# BackPage.net
KiCad netlist of a schematic drawn in Altium Designer
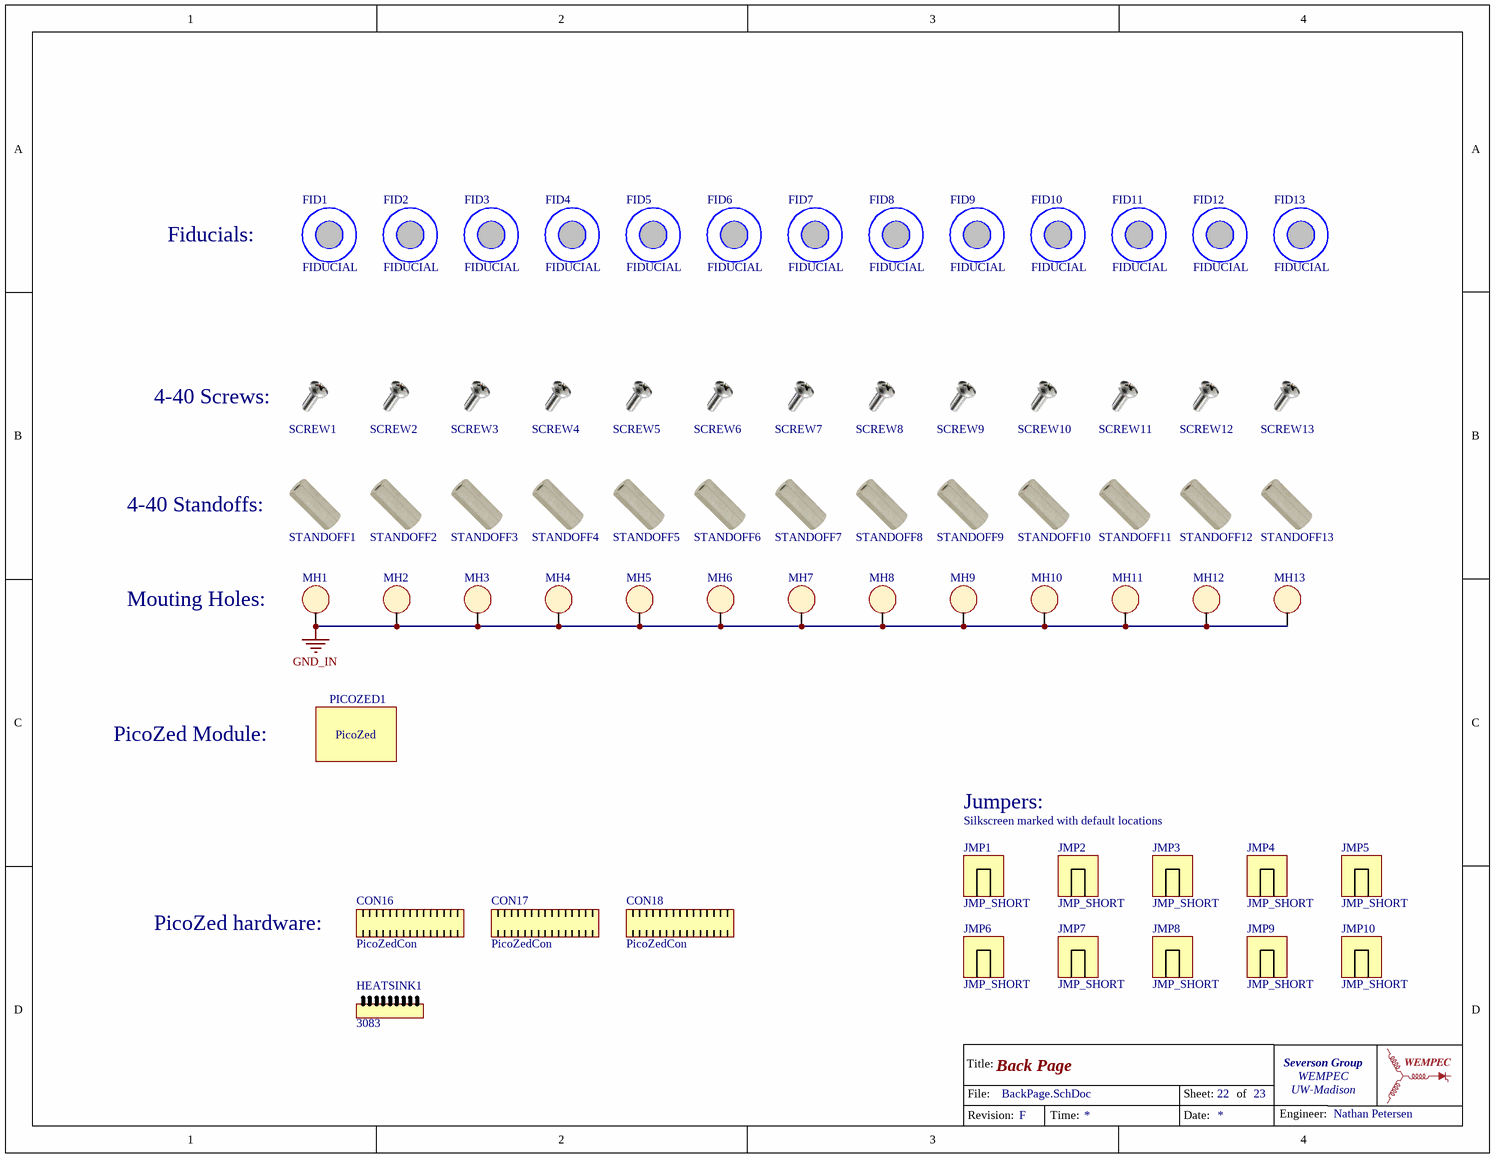
[diagram p0: BackPage.SchDoc]

(export (version "E")
  (design (tool "Eeschema 10.0.6"))
  (components
    (comp (ref "CON16")
      (value "PicoZedCon")
      (description "CONN HEADER 100POS .8MM DUAL SMD")
      (libsource (lib "AMDC") (part "PicoZedCon"))
    )
    (comp (ref "CON17")
      (value "PicoZedCon")
      (description "CONN HEADER 100POS .8MM DUAL SMD")
      (libsource (lib "AMDC") (part "PicoZedCon"))
    )
    (comp (ref "CON18")
      (value "PicoZedCon")
      (description "CONN HEADER 100POS .8MM DUAL SMD")
      (libsource (lib "AMDC") (part "PicoZedCon"))
    )
    (comp (ref "FID1") (value "FIDUCIAL") (footprint "FID_1mm") (libsource (lib "AMDC") (part "FIDUCIAL")))
    (comp (ref "FID2") (value "FIDUCIAL") (footprint "FID_1mm") (libsource (lib "AMDC") (part "FIDUCIAL")))
    (comp (ref "FID3") (value "FIDUCIAL") (footprint "FID_1mm") (libsource (lib "AMDC") (part "FIDUCIAL")))
    (comp (ref "FID4") (value "FIDUCIAL") (footprint "FID_1mm") (libsource (lib "AMDC") (part "FIDUCIAL")))
    (comp (ref "FID5") (value "FIDUCIAL") (footprint "FID_1mm") (libsource (lib "AMDC") (part "FIDUCIAL")))
    (comp (ref "FID6") (value "FIDUCIAL") (footprint "FID_1mm") (libsource (lib "AMDC") (part "FIDUCIAL")))
    (comp (ref "FID7") (value "FIDUCIAL") (footprint "FID_1mm") (libsource (lib "AMDC") (part "FIDUCIAL")))
    (comp (ref "FID8") (value "FIDUCIAL") (footprint "FID_1mm") (libsource (lib "AMDC") (part "FIDUCIAL")))
    (comp (ref "FID9") (value "FIDUCIAL") (footprint "FID_1mm") (libsource (lib "AMDC") (part "FIDUCIAL")))
    (comp (ref "FID10") (value "FIDUCIAL") (footprint "FID_1mm") (libsource (lib "AMDC") (part "FIDUCIAL")))
    (comp (ref "FID11") (value "FIDUCIAL") (footprint "FID_1mm") (libsource (lib "AMDC") (part "FIDUCIAL")))
    (comp (ref "FID12") (value "FIDUCIAL") (footprint "FID_1mm") (libsource (lib "AMDC") (part "FIDUCIAL")))
    (comp (ref "FID13") (value "FIDUCIAL") (footprint "FID_1mm") (libsource (lib "AMDC") (part "FIDUCIAL")))
    (comp (ref "HEATSINK1")
      (value "3083")
      (description "ALUM HEAT SINK FOR RASPBERRY PI")
      (libsource (lib "AMDC") (part "PicoZedHeatSink"))
    )
    (comp (ref "JMP1")
      (value "JMP_SHORT")
      (description "CONN JUMPER SHORTING .100\" GOLD")
      (libsource (lib "AMDC") (part "JUMPER_SHORT"))
    )
    (comp (ref "JMP2")
      (value "JMP_SHORT")
      (description "CONN JUMPER SHORTING .100\" GOLD")
      (libsource (lib "AMDC") (part "JUMPER_SHORT"))
    )
    (comp (ref "JMP3")
      (value "JMP_SHORT")
      (description "CONN JUMPER SHORTING .100\" GOLD")
      (libsource (lib "AMDC") (part "JUMPER_SHORT"))
    )
    (comp (ref "JMP4")
      (value "JMP_SHORT")
      (description "CONN JUMPER SHORTING .100\" GOLD")
      (libsource (lib "AMDC") (part "JUMPER_SHORT"))
    )
    (comp (ref "JMP5")
      (value "JMP_SHORT")
      (description "CONN JUMPER SHORTING .100\" GOLD")
      (libsource (lib "AMDC") (part "JUMPER_SHORT"))
    )
    (comp (ref "JMP6")
      (value "JMP_SHORT")
      (description "CONN JUMPER SHORTING .100\" GOLD")
      (libsource (lib "AMDC") (part "JUMPER_SHORT"))
    )
    (comp (ref "JMP7")
      (value "JMP_SHORT")
      (description "CONN JUMPER SHORTING .100\" GOLD")
      (libsource (lib "AMDC") (part "JUMPER_SHORT"))
    )
    (comp (ref "JMP8")
      (value "JMP_SHORT")
      (description "CONN JUMPER SHORTING .100\" GOLD")
      (libsource (lib "AMDC") (part "JUMPER_SHORT"))
    )
    (comp (ref "JMP9")
      (value "JMP_SHORT")
      (description "CONN JUMPER SHORTING .100\" GOLD")
      (libsource (lib "AMDC") (part "JUMPER_SHORT"))
    )
    (comp (ref "JMP10")
      (value "JMP_SHORT")
      (description "CONN JUMPER SHORTING .100\" GOLD")
      (libsource (lib "AMDC") (part "JUMPER_SHORT"))
    )
    (comp (ref "MH1")
      (value "MOUNT_HOLE")
      (footprint "MOUNTING_HOLE")
      (description "MOUNTING HOLE")
      (libsource (lib "AMDC") (part "MOUNT_HOLE"))
    )
    (comp (ref "MH2")
      (value "MOUNT_HOLE")
      (footprint "MOUNTING_HOLE")
      (description "MOUNTING HOLE")
      (libsource (lib "AMDC") (part "MOUNT_HOLE"))
    )
    (comp (ref "MH3")
      (value "MOUNT_HOLE")
      (footprint "MOUNTING_HOLE")
      (description "MOUNTING HOLE")
      (libsource (lib "AMDC") (part "MOUNT_HOLE"))
    )
    (comp (ref "MH4")
      (value "MOUNT_HOLE")
      (footprint "MOUNTING_HOLE")
      (description "MOUNTING HOLE")
      (libsource (lib "AMDC") (part "MOUNT_HOLE"))
    )
    (comp (ref "MH5")
      (value "MOUNT_HOLE")
      (footprint "MOUNTING_HOLE")
      (description "MOUNTING HOLE")
      (libsource (lib "AMDC") (part "MOUNT_HOLE"))
    )
    (comp (ref "MH6")
      (value "MOUNT_HOLE")
      (footprint "MOUNTING_HOLE")
      (description "MOUNTING HOLE")
      (libsource (lib "AMDC") (part "MOUNT_HOLE"))
    )
    (comp (ref "MH7")
      (value "MOUNT_HOLE")
      (footprint "MOUNTING_HOLE")
      (description "MOUNTING HOLE")
      (libsource (lib "AMDC") (part "MOUNT_HOLE"))
    )
    (comp (ref "MH8")
      (value "MOUNT_HOLE")
      (footprint "MOUNTING_HOLE")
      (description "MOUNTING HOLE")
      (libsource (lib "AMDC") (part "MOUNT_HOLE"))
    )
    (comp (ref "MH9")
      (value "MOUNT_HOLE")
      (footprint "MOUNTING_HOLE")
      (description "MOUNTING HOLE")
      (libsource (lib "AMDC") (part "MOUNT_HOLE"))
    )
    (comp (ref "MH10")
      (value "MOUNT_HOLE")
      (footprint "MOUNTING_HOLE")
      (description "MOUNTING HOLE")
      (libsource (lib "AMDC") (part "MOUNT_HOLE"))
    )
    (comp (ref "MH11")
      (value "MOUNT_HOLE")
      (footprint "MOUNTING_HOLE")
      (description "MOUNTING HOLE")
      (libsource (lib "AMDC") (part "MOUNT_HOLE"))
    )
    (comp (ref "MH12")
      (value "MOUNT_HOLE")
      (footprint "MOUNTING_HOLE")
      (description "MOUNTING HOLE")
      (libsource (lib "AMDC") (part "MOUNT_HOLE"))
    )
    (comp (ref "MH13")
      (value "MOUNT_HOLE")
      (footprint "MOUNTING_HOLE")
      (description "MOUNTING HOLE")
      (libsource (lib "AMDC") (part "MOUNT_HOLE"))
    )
    (comp (ref "PICOZED1")
      (value "7Z030-PicoZed")
      (description "PicoZed 7030 SOM Evaluation Board with ARM Cortex-A9 1 x 10/100/1000 eMMC/QSPI Flash")
      (libsource (lib "AMDC") (part "7Z030-PicoZed"))
    )
    (comp (ref "SCREW1") (value "Screw-4-40") (libsource (lib "AMDC") (part "Screw-4-40")))
    (comp (ref "SCREW2") (value "Screw-4-40") (libsource (lib "AMDC") (part "Screw-4-40")))
    (comp (ref "SCREW3") (value "Screw-4-40") (libsource (lib "AMDC") (part "Screw-4-40")))
    (comp (ref "SCREW4") (value "Screw-4-40") (libsource (lib "AMDC") (part "Screw-4-40")))
    (comp (ref "SCREW5") (value "Screw-4-40") (libsource (lib "AMDC") (part "Screw-4-40")))
    (comp (ref "SCREW6") (value "Screw-4-40") (libsource (lib "AMDC") (part "Screw-4-40")))
    (comp (ref "SCREW7") (value "Screw-4-40") (libsource (lib "AMDC") (part "Screw-4-40")))
    (comp (ref "SCREW8") (value "Screw-4-40") (libsource (lib "AMDC") (part "Screw-4-40")))
    (comp (ref "SCREW9") (value "Screw-4-40") (libsource (lib "AMDC") (part "Screw-4-40")))
    (comp (ref "SCREW10") (value "Screw-4-40") (libsource (lib "AMDC") (part "Screw-4-40")))
    (comp (ref "SCREW11") (value "Screw-4-40") (libsource (lib "AMDC") (part "Screw-4-40")))
    (comp (ref "SCREW12") (value "Screw-4-40") (libsource (lib "AMDC") (part "Screw-4-40")))
    (comp (ref "SCREW13") (value "Screw-4-40") (libsource (lib "AMDC") (part "Screw-4-40")))
    (comp (ref "STANDOFF1") (value "Standoff-4-40") (libsource (lib "AMDC") (part "Standoff-4-40")))
    (comp (ref "STANDOFF2") (value "Standoff-4-40") (libsource (lib "AMDC") (part "Standoff-4-40")))
    (comp (ref "STANDOFF3") (value "Standoff-4-40") (libsource (lib "AMDC") (part "Standoff-4-40")))
    (comp (ref "STANDOFF4") (value "Standoff-4-40") (libsource (lib "AMDC") (part "Standoff-4-40")))
    (comp (ref "STANDOFF5") (value "Standoff-4-40") (libsource (lib "AMDC") (part "Standoff-4-40")))
    (comp (ref "STANDOFF6") (value "Standoff-4-40") (libsource (lib "AMDC") (part "Standoff-4-40")))
    (comp (ref "STANDOFF7") (value "Standoff-4-40") (libsource (lib "AMDC") (part "Standoff-4-40")))
    (comp (ref "STANDOFF8") (value "Standoff-4-40") (libsource (lib "AMDC") (part "Standoff-4-40")))
    (comp (ref "STANDOFF9") (value "Standoff-4-40") (libsource (lib "AMDC") (part "Standoff-4-40")))
    (comp (ref "STANDOFF10") (value "Standoff-4-40") (libsource (lib "AMDC") (part "Standoff-4-40")))
    (comp (ref "STANDOFF11") (value "Standoff-4-40") (libsource (lib "AMDC") (part "Standoff-4-40")))
    (comp (ref "STANDOFF12") (value "Standoff-4-40") (libsource (lib "AMDC") (part "Standoff-4-40")))
    (comp (ref "STANDOFF13") (value "Standoff-4-40") (libsource (lib "AMDC") (part "Standoff-4-40")))
  )
  (nets
    (net (code "1") (name "GND_IN") (class "Default")
      (node (ref "MH1") (pin "1") (pinfunction "1_1") (pintype "passive"))
      (node (ref "MH10") (pin "1") (pinfunction "1_1") (pintype "passive"))
      (node (ref "MH11") (pin "1") (pinfunction "1_1") (pintype "passive"))
      (node (ref "MH12") (pin "1") (pinfunction "1_1") (pintype "passive"))
      (node (ref "MH13") (pin "1") (pinfunction "1_1") (pintype "passive"))
      (node (ref "MH2") (pin "1") (pinfunction "1_1") (pintype "passive"))
      (node (ref "MH3") (pin "1") (pinfunction "1_1") (pintype "passive"))
      (node (ref "MH4") (pin "1") (pinfunction "1_1") (pintype "passive"))
      (node (ref "MH5") (pin "1") (pinfunction "1_1") (pintype "passive"))
      (node (ref "MH6") (pin "1") (pinfunction "1_1") (pintype "passive"))
      (node (ref "MH7") (pin "1") (pinfunction "1_1") (pintype "passive"))
      (node (ref "MH8") (pin "1") (pinfunction "1_1") (pintype "passive"))
      (node (ref "MH9") (pin "1") (pinfunction "1_1") (pintype "passive"))
    )
  )
)
